# Sheet1.net
KiCad netlist of a schematic drawn in Altium Designer
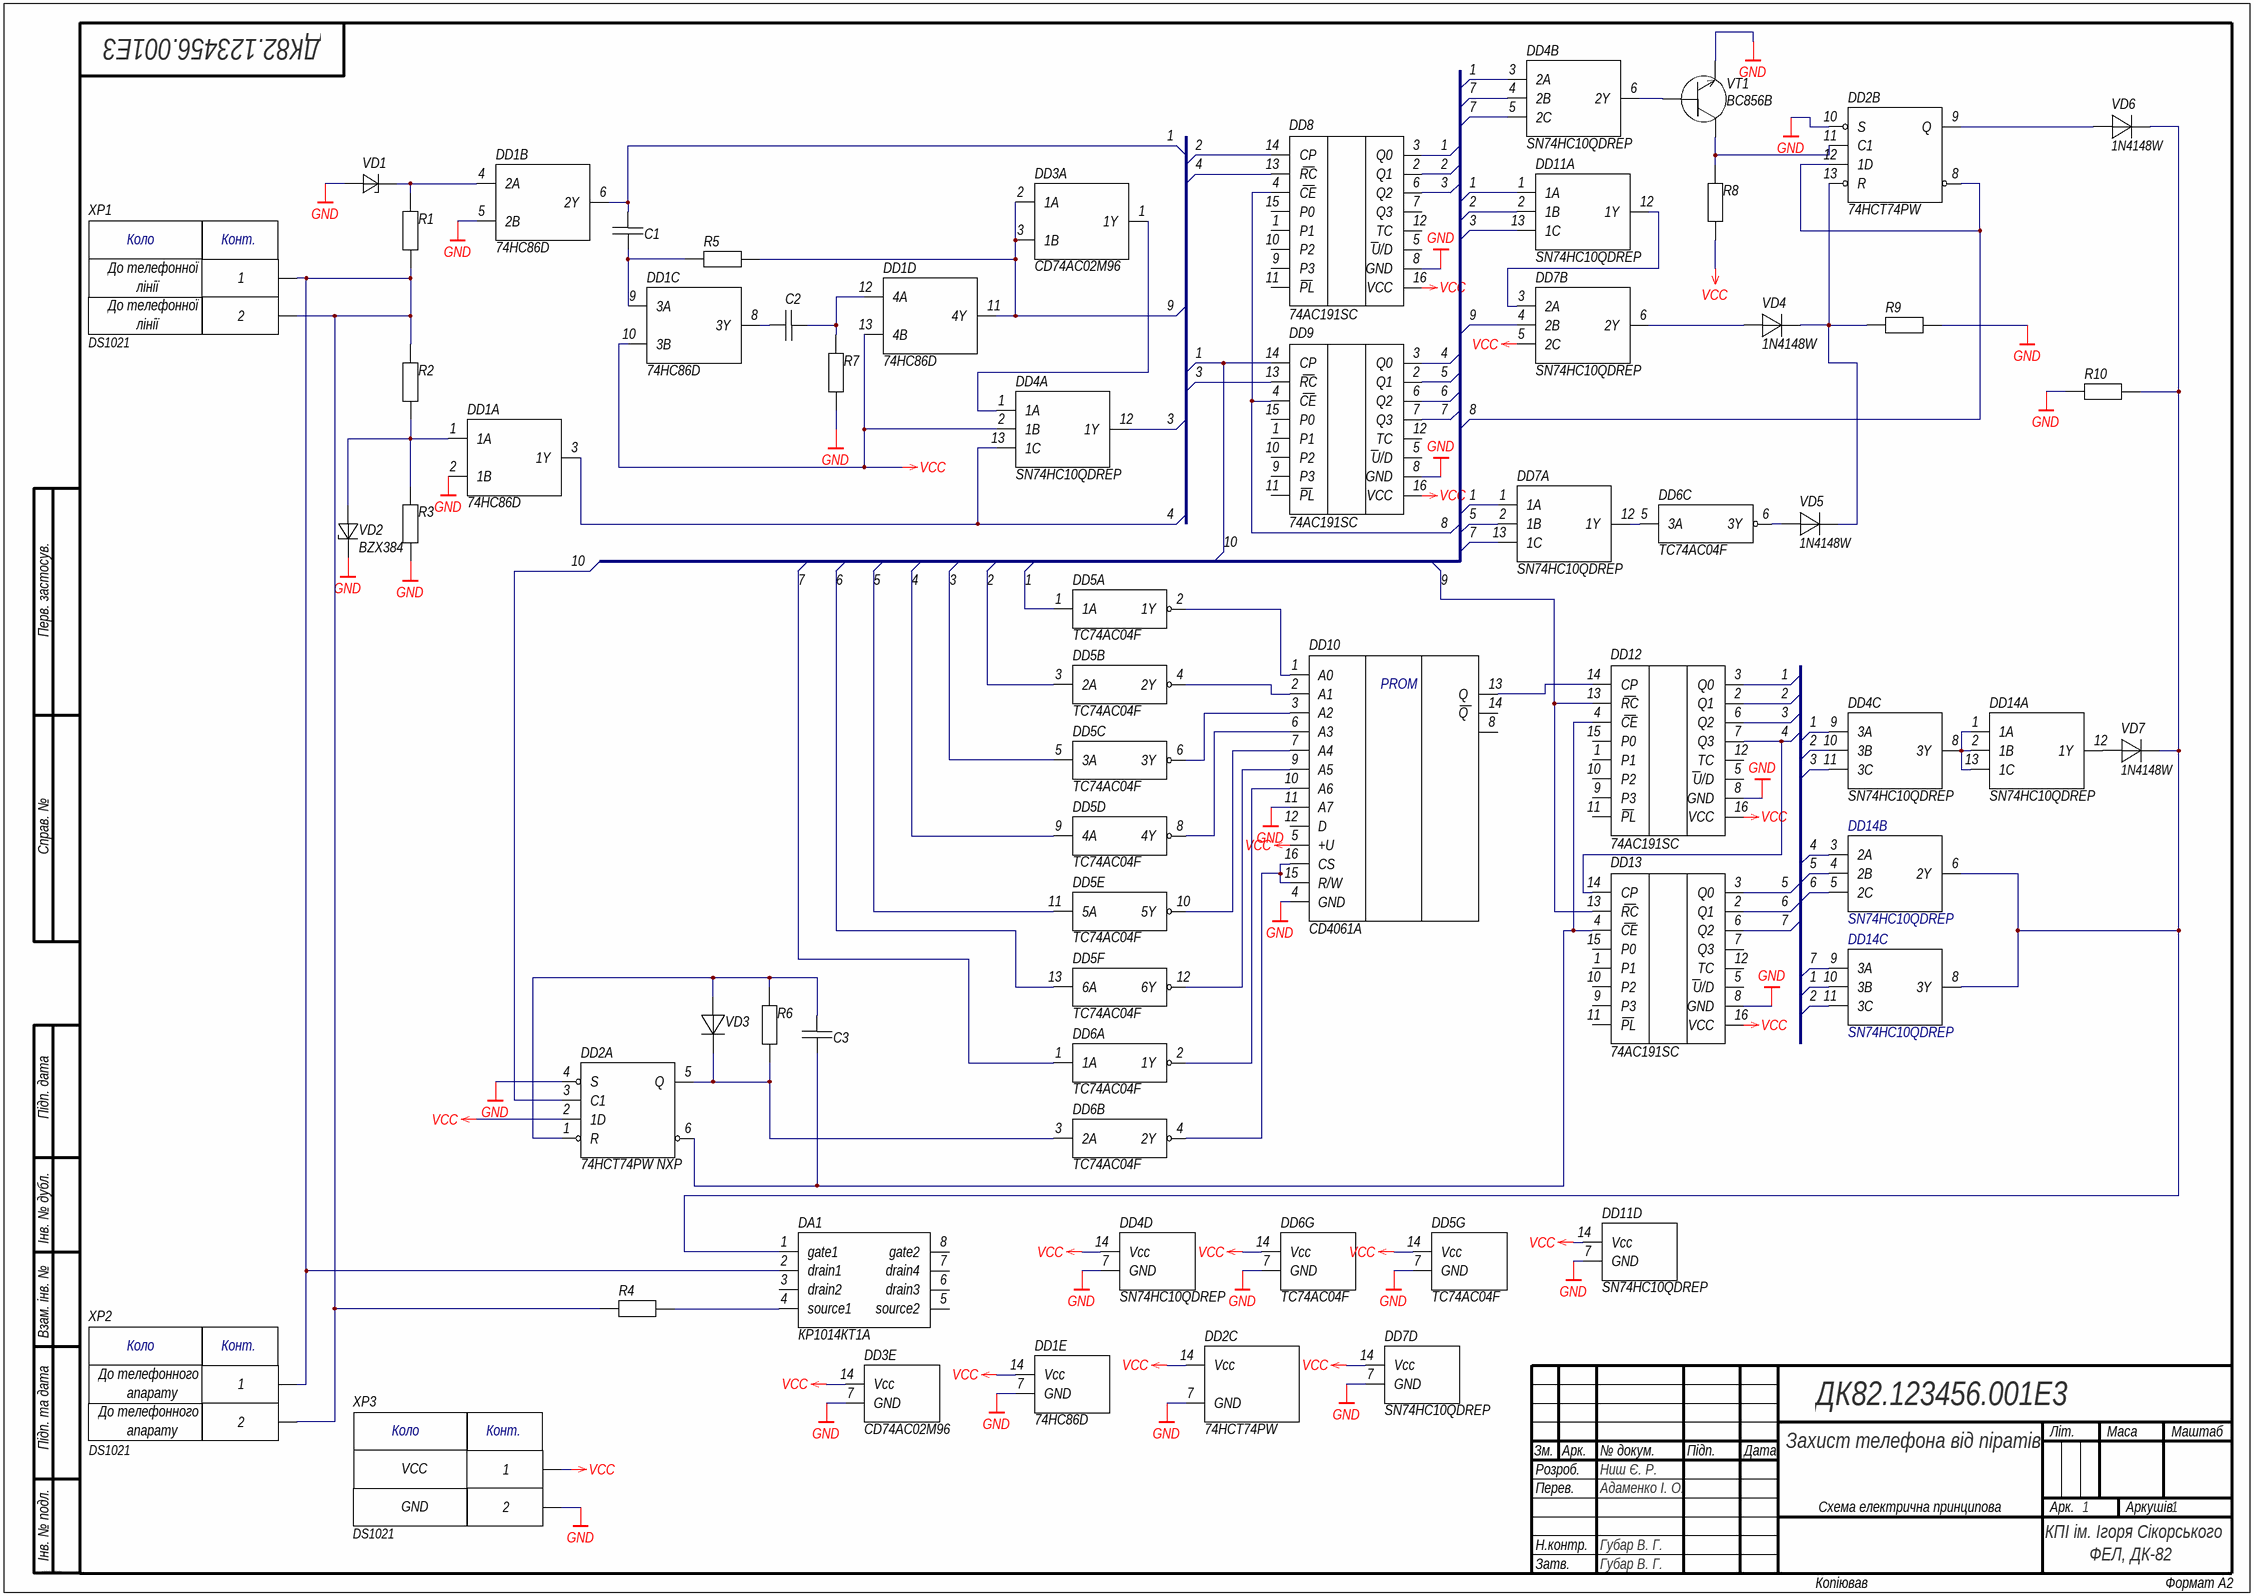
[diagram p0: Sheet1.SchDoc]

(export (version "E")
  (design (tool "Eeschema 10.0.6"))
  (components
    (comp (ref "C1")
      (value "С-0805 50 В 1 мкФ 10% X7R Hitano")
      (footprint "0805")
      (fields
        (field (name "VOLTAGE") "50 В")
        (field (name "TOLERANCE") "10%")
        (field (name "MANUFACTURER") "Hitano")
      )
      (libsource (lib "Schlib1") (part "C-0805 1 мкФ"))
    )
    (comp (ref "C2")
      (value "С-0805 50 В 1 мкФ 10% X7R Hitano")
      (footprint "0805")
      (fields
        (field (name "VOLTAGE") "50 В")
        (field (name "TOLERANCE") "10%")
        (field (name "MANUFACTURER") "Hitano")
      )
      (libsource (lib "Schlib1") (part "C-0805 1 мкФ"))
    )
    (comp (ref "C3")
      (value "С-0805 50 В 1 мкФ 10% X7R Hitano")
      (footprint "0805")
      (fields
        (field (name "VOLTAGE") "50 В")
        (field (name "TOLERANCE") "10%")
        (field (name "MANUFACTURER") "Hitano")
      )
      (libsource (lib "Schlib1") (part "C-0805 1 мкФ"))
    )
    (comp (ref "DA1")
      (value "КР1014КТ1А Электроника и связь")
      (footprint "DIP8")
      (fields (field (name "NAME") "КР1014КТ1А") (field (name "MANUFACTURER") "Электроника и связь"))
      (libsource (lib "Schlib1") (part "КР1014КТ1А"))
    )
    (comp (ref "DD1")
      (value "74HC86D Philips")
      (footprint "SOIC-14")
      (description "OR")
      (fields (field (name "NAME") "74HC86D") (field (name "MANUFACTURER") "Philips"))
      (libsource (lib "Schlib1") (part "74HC86D"))
    )
    (comp (ref "DD2")
      (value "74HCT74PW NXP")
      (footprint "TSSOP-14")
      (description "DUAL D FF POSEDG TRIG")
      (fields (field (name "MANUFACTURER") "NXP") (field (name "NAME") "74HCT74PW"))
      (libsource (lib "Schlib1") (part "74HCT74PW"))
    )
    (comp (ref "DD3")
      (value "CD74AC02M96 TI")
      (footprint "SOIC-14")
      (description "2-INPUT NOR GATE")
      (fields (field (name "NAME") "CD74AC02M96") (field (name "MANUFACTURER") "TI"))
      (libsource (lib "Schlib1") (part "CD74AC02M96"))
    )
    (comp (ref "DD4")
      (value "SN74HC10QDREP Texas Instruments")
      (footprint "SOIC-14")
      (description "3-INPUT NAND GATE")
      (fields (field (name "NAME") "SN74HC10QDREP") (field (name "MANUFACTURER") "Texas Instruments"))
      (libsource (lib "Schlib1") (part "SN74HC10QDREP"))
    )
    (comp (ref "DD5")
      (value "TC74AC04F Toshiba")
      (footprint "SOIC-14")
      (description "NOT")
      (fields (field (name "NAME") "TC74AC04F") (field (name "MANUFACTURER") "Toshiba"))
      (libsource (lib "Schlib1") (part "TC74AC04F"))
    )
    (comp (ref "DD6")
      (value "TC74AC04F Toshiba")
      (footprint "SOIC-14")
      (description "NOT")
      (fields (field (name "NAME") "TC74AC04F") (field (name "MANUFACTURER") "Toshiba"))
      (libsource (lib "Schlib1") (part "TC74AC04F"))
    )
    (comp (ref "DD7")
      (value "SN74HC10QDREP Texas Instruments")
      (footprint "SOIC-14")
      (description "3-INPUT NAND GATE")
      (fields (field (name "NAME") "SN74HC10QDREP") (field (name "MANUFACTURER") "Texas Instruments"))
      (libsource (lib "Schlib1") (part "SN74HC10QDREP"))
    )
    (comp (ref "DD8")
      (value "74AC191SC Fairchild")
      (footprint "SOIC-16")
      (description "Counter")
      (fields (field (name "NAME") "74AC191SC") (field (name "MANUFACTURER") "Fairchild"))
      (libsource (lib "Schlib1") (part "74AC191SC"))
    )
    (comp (ref "DD9")
      (value "74AC191SC Fairchild")
      (footprint "SOIC-16")
      (description "Counter")
      (fields (field (name "NAME") "74AC191SC") (field (name "MANUFACTURER") "Fairchild"))
      (libsource (lib "Schlib1") (part "74AC191SC"))
    )
    (comp (ref "DD10")
      (value "CD4061A NXP")
      (footprint "DIP16")
      (fields (field (name "NAME") "CD4061A") (field (name "MANUFACTURER") "NXP"))
      (libsource (lib "Schlib1") (part "CD4061A"))
    )
    (comp (ref "DD11")
      (value "SN74HC10QDREP Texas Instruments")
      (footprint "SOIC-14")
      (description "3-INPUT NAND GATE")
      (fields (field (name "NAME") "SN74HC10QDREP") (field (name "MANUFACTURER") "Texas Instruments"))
      (libsource (lib "Schlib1") (part "SN74HC10QDREP"))
    )
    (comp (ref "DD12")
      (value "74AC191SC Fairchild")
      (footprint "SOIC-16")
      (description "Counter")
      (fields (field (name "NAME") "74AC191SC") (field (name "MANUFACTURER") "Fairchild"))
      (libsource (lib "Schlib1") (part "74AC191SC"))
    )
    (comp (ref "DD13")
      (value "74AC191SC Fairchild")
      (footprint "SOIC-16")
      (description "Counter")
      (fields (field (name "NAME") "74AC191SC") (field (name "MANUFACTURER") "Fairchild"))
      (libsource (lib "Schlib1") (part "74AC191SC"))
    )
    (comp (ref "DD14")
      (value "SN74HC10QDREP Texas Instruments")
      (footprint "SOIC-14")
      (description "3-INPUT NAND GATE")
      (fields (field (name "NAME") "SN74HC10QDREP") (field (name "MANUFACTURER") "Texas Instruments"))
      (libsource (lib "Schlib1") (part "SN74HC10QDREP"))
    )
    (comp (ref "R1")
      (value "R-0805 0,125 Вт 390 кОм 5 % Hitano")
      (footprint "0805")
      (fields
        (field (name "POWER") "0,125 Вт")
        (field (name "TOLERANCE") "5 %")
        (field (name "MANUFACTURER") "Hitano")
      )
      (libsource (lib "Schlib1") (part "R-0805 390 кОм"))
    )
    (comp (ref "R2")
      (value "R-0805 0,125 Вт 433,5 кОм 5 % Hitano")
      (footprint "0805")
      (fields
        (field (name "POWER") "0,125 Вт")
        (field (name "TOLERANCE") "5 %")
        (field (name "MANUFACTURER") "Hitano")
      )
      (libsource (lib "Schlib1") (part "R-0805 433,5 кОм"))
    )
    (comp (ref "R3")
      (value "R-0805 0,125 Вт 76,5 кОм 5 % Hitano")
      (footprint "0805")
      (fields
        (field (name "POWER") "0,125 Вт")
        (field (name "TOLERANCE") "5 %")
        (field (name "MANUFACTURER") "Hitano")
      )
      (libsource (lib "Schlib1") (part "R-0805 76,5 кОм"))
    )
    (comp (ref "R4")
      (value "R-0805 0,125 Вт 39 кОм 5 % Hitano")
      (footprint "0805")
      (fields
        (field (name "POWER") "0,125 Вт")
        (field (name "TOLERANCE") "5 %")
        (field (name "MANUFACTURER") "Hitano")
      )
      (libsource (lib "Schlib1") (part "R-0805 39 кОм"))
    )
    (comp (ref "R5")
      (value "R-0805 0,125 Вт 100 кОм 5 % Hitano")
      (footprint "0805")
      (fields
        (field (name "POWER") "0,125 Вт")
        (field (name "TOLERANCE") "5 %")
        (field (name "MANUFACTURER") "Hitano")
      )
      (libsource (lib "Schlib1") (part "R-0805 100 кОм"))
    )
    (comp (ref "R6")
      (value "R-0805 0,125 Вт 82 кОм 5 % Hitano")
      (footprint "0805")
      (fields
        (field (name "POWER") "0,125 Вт")
        (field (name "TOLERANCE") "5 %")
        (field (name "MANUFACTURER") "Hitano")
      )
      (libsource (lib "") (part "R-0805 82 кОм_1"))
    )
    (comp (ref "R7")
      (value "R-0805 0,125 Вт 82 кОм 5 % Hitano")
      (footprint "0805")
      (fields
        (field (name "POWER") "0,125 Вт")
        (field (name "TOLERANCE") "5 %")
        (field (name "MANUFACTURER") "Hitano")
      )
      (libsource (lib "Schlib1") (part "R-0805 82 кОм"))
    )
    (comp (ref "R8")
      (value "R-0805 0,125 Вт 100 кОм 5 % Hitano")
      (footprint "0805")
      (fields
        (field (name "POWER") "0,125 Вт")
        (field (name "TOLERANCE") "5 %")
        (field (name "MANUFACTURER") "Hitano")
      )
      (libsource (lib "") (part "R-0805 100 кОм_1"))
    )
    (comp (ref "R9")
      (value "R-0805 0,125 Вт 100 кОм 5 % Hitano")
      (footprint "0805")
      (fields
        (field (name "POWER") "0,125 Вт")
        (field (name "TOLERANCE") "5 %")
        (field (name "MANUFACTURER") "Hitano")
      )
      (libsource (lib "Schlib1") (part "R-0805 100 кОм"))
    )
    (comp (ref "R10")
      (value "R-0805 0,125 Вт 100 кОм 5 % Hitano")
      (footprint "0805")
      (fields
        (field (name "POWER") "0,125 Вт")
        (field (name "TOLERANCE") "5 %")
        (field (name "MANUFACTURER") "Hitano")
      )
      (libsource (lib "Schlib1") (part "R-0805 100 кОм"))
    )
    (comp (ref "VD1")
      (value "BZX384 NXP")
      (footprint "SOD-323")
      (fields (field (name "MANUFACTURER") "NXP"))
      (libsource (lib "Schlib1") (part "BZX384"))
    )
    (comp (ref "VD2")
      (value "BZX384 NXP")
      (footprint "SOD-323")
      (fields (field (name "NAME") "BZX384") (field (name "MANUFACTURER") "NXP"))
      (libsource (lib "Schlib1") (part "BZX384"))
    )
    (comp (ref "VD3")
      (value "1N4148W Yangjie")
      (footprint "SOD-123")
      (description "1N4148W")
      (fields (field (name "MANUFACTURER") "Yangjie"))
      (libsource (lib "Schlib1") (part "1N4148W"))
    )
    (comp (ref "VD4")
      (value "1N4148W Yangjie")
      (footprint "SOD-123")
      (description "1N4148W")
      (fields (field (name "MANUFACTURER") "Yangjie") (field (name "NAME") "1N4148W"))
      (libsource (lib "Schlib1") (part "1N4148W"))
    )
    (comp (ref "VD5")
      (value "1N4148W Yangjie")
      (footprint "SOD-123")
      (description "1N4148W")
      (fields (field (name "MANUFACTURER") "Yangjie") (field (name "NAME") "1N4148W"))
      (libsource (lib "Schlib1") (part "1N4148W"))
    )
    (comp (ref "VD6")
      (value "1N4148W Yangjie")
      (footprint "SOD-123")
      (description "1N4148W")
      (fields (field (name "MANUFACTURER") "Yangjie") (field (name "NAME") "1N4148W"))
      (libsource (lib "Schlib1") (part "1N4148W"))
    )
    (comp (ref "VD7")
      (value "1N4148W Yangjie")
      (footprint "SOD-123")
      (description "1N4148W")
      (fields (field (name "MANUFACTURER") "Yangjie") (field (name "NAME") "1N4148W"))
      (libsource (lib "Schlib1") (part "1N4148W"))
    )
    (comp (ref "VT1")
      (value "BC856B Infineon")
      (footprint "SOT-23")
      (fields (field (name "NAME") "BC856B") (field (name "MANUFACTURER") "Infineon"))
      (libsource (lib "Schlib1") (part "BC856B"))
    )
    (comp (ref "XP1")
      (value "DS1021 Ningbo Zhenqin Electronic")
      (footprint "PLS-2")
      (description "PLS-2_1x2")
      (fields (field (name "MANUFACTURER") "Ningbo Zhenqin Electronic") (field (name "NAME") "DS1021"))
      (libsource (lib "Schlib1") (part "DS1021"))
    )
    (comp (ref "XP2")
      (value "DS1021 Ningbo Zhenqin Electronic")
      (footprint "PLS-2")
      (description "PLS-2_1x2")
      (fields (field (name "MANUFACTURER") "Ningbo Zhenqin Electronic") (field (name "NAME") "DS1021"))
      (libsource (lib "Schlib1") (part "DS1021"))
    )
    (comp (ref "XP3")
      (value "DS1021 Ningbo Zhenqin Electronic")
      (footprint "PLS-2")
      (description "PLS-2_1x2")
      (fields (field (name "MANUFACTURER") "Ningbo Zhenqin Electronic") (field (name "NAME") "DS1021"))
      (libsource (lib "Schlib1") (part "DS1021"))
    )
  )
  (nets
    (net (code "1") (name "/1") (class "Default")
      (node (ref "C1") (pin "2") (pintype "passive"))
      (node (ref "DD1") (pin "6") (pinfunction "2Y_6") (pintype "passive"))
      (node (ref "DD11") (pin "1") (pinfunction "1A_1") (pintype "passive"))
      (node (ref "DD12") (pin "3") (pinfunction "Q0_3") (pintype "passive"))
      (node (ref "DD14") (pin "10") (pinfunction "3B_10") (pintype "passive"))
      (node (ref "DD2") (pin "3") (pinfunction "C1_3") (pintype "passive"))
      (node (ref "DD4") (pin "3") (pinfunction "2A_3") (pintype "passive"))
      (node (ref "DD4") (pin "9") (pinfunction "3A_9") (pintype "passive"))
      (node (ref "DD5") (pin "1") (pinfunction "1A_1") (pintype "passive"))
      (node (ref "DD7") (pin "1") (pinfunction "1A_1") (pintype "passive"))
      (node (ref "DD8") (pin "3") (pinfunction "Q0_3") (pintype "passive"))
      (node (ref "DD9") (pin "14") (pinfunction "CP_14") (pintype "passive"))
    )
    (net (code "2") (name "/2") (class "Default")
      (node (ref "DD11") (pin "2") (pinfunction "1B_2") (pintype "passive"))
      (node (ref "DD12") (pin "2") (pinfunction "Q1_2") (pintype "passive"))
      (node (ref "DD14") (pin "11") (pinfunction "3C_11") (pintype "passive"))
      (node (ref "DD4") (pin "10") (pinfunction "3B_10") (pintype "passive"))
      (node (ref "DD5") (pin "3") (pinfunction "2A_3") (pintype "passive"))
      (node (ref "DD8") (pin "14") (pinfunction "CP_14") (pintype "passive"))
      (node (ref "DD8") (pin "2") (pinfunction "Q1_2") (pintype "passive"))
    )
    (net (code "3") (name "/3") (class "Default")
      (node (ref "DD11") (pin "13") (pinfunction "1C_13") (pintype "passive"))
      (node (ref "DD12") (pin "6") (pinfunction "Q2_6") (pintype "passive"))
      (node (ref "DD4") (pin "11") (pinfunction "3C_11") (pintype "passive"))
      (node (ref "DD4") (pin "12") (pinfunction "1Y_12") (pintype "passive"))
      (node (ref "DD5") (pin "5") (pinfunction "3A_5") (pintype "passive"))
      (node (ref "DD8") (pin "6") (pinfunction "Q2_6") (pintype "passive"))
      (node (ref "DD9") (pin "13") (pinfunction "RC_13") (pintype "passive"))
    )
    (net (code "4") (name "/4") (class "Default")
      (node (ref "DD1") (pin "3") (pinfunction "1Y_3") (pintype "passive"))
      (node (ref "DD12") (pin "7") (pinfunction "Q3_7") (pintype "passive"))
      (node (ref "DD13") (pin "14") (pinfunction "CP_14") (pintype "passive"))
      (node (ref "DD14") (pin "3") (pinfunction "2A_3") (pintype "passive"))
      (node (ref "DD4") (pin "13") (pinfunction "1C_13") (pintype "passive"))
      (node (ref "DD5") (pin "9") (pinfunction "4A_9") (pintype "passive"))
      (node (ref "DD8") (pin "13") (pinfunction "RC_13") (pintype "passive"))
      (node (ref "DD9") (pin "3") (pinfunction "Q0_3") (pintype "passive"))
    )
    (net (code "5") (name "/5") (class "Default")
      (node (ref "DD13") (pin "3") (pinfunction "Q0_3") (pintype "passive"))
      (node (ref "DD14") (pin "4") (pinfunction "2B_4") (pintype "passive"))
      (node (ref "DD5") (pin "11") (pinfunction "5A_11") (pintype "passive"))
      (node (ref "DD7") (pin "2") (pinfunction "1B_2") (pintype "passive"))
      (node (ref "DD9") (pin "2") (pinfunction "Q1_2") (pintype "passive"))
    )
    (net (code "6") (name "/6") (class "Default")
      (node (ref "DD13") (pin "2") (pinfunction "Q1_2") (pintype "passive"))
      (node (ref "DD14") (pin "5") (pinfunction "2C_5") (pintype "passive"))
      (node (ref "DD5") (pin "13") (pinfunction "6A_13") (pintype "passive"))
      (node (ref "DD9") (pin "6") (pinfunction "Q2_6") (pintype "passive"))
    )
    (net (code "7") (name "/7") (class "Default")
      (node (ref "DD13") (pin "6") (pinfunction "Q2_6") (pintype "passive"))
      (node (ref "DD14") (pin "9") (pinfunction "3A_9") (pintype "passive"))
      (node (ref "DD4") (pin "4") (pinfunction "2B_4") (pintype "passive"))
      (node (ref "DD4") (pin "5") (pinfunction "2C_5") (pintype "passive"))
      (node (ref "DD6") (pin "1") (pinfunction "1A_1") (pintype "passive"))
      (node (ref "DD7") (pin "13") (pinfunction "1C_13") (pintype "passive"))
      (node (ref "DD9") (pin "7") (pinfunction "Q3_7") (pintype "passive"))
    )
    (net (code "8") (name "/8") (class "Default")
      (node (ref "DD2") (pin "12") (pinfunction "1D_12") (pintype "passive"))
      (node (ref "DD2") (pin "8") (pinfunction "Q_8") (pintype "passive"))
      (node (ref "DD8") (pin "4") (pinfunction "CE_4") (pintype "passive"))
      (node (ref "DD9") (pin "4") (pinfunction "CE_4") (pintype "passive"))
    )
    (net (code "9") (name "/9") (class "Default")
      (node (ref "DD1") (pin "11") (pinfunction "4Y_11") (pintype "passive"))
      (node (ref "DD12") (pin "13") (pinfunction "RC_13") (pintype "passive"))
      (node (ref "DD13") (pin "13") (pinfunction "RC_13") (pintype "passive"))
      (node (ref "DD3") (pin "2") (pinfunction "1A_2") (pintype "passive"))
      (node (ref "DD3") (pin "3") (pinfunction "1B_3") (pintype "passive"))
      (node (ref "DD7") (pin "4") (pinfunction "2B_4") (pintype "passive"))
      (node (ref "R5") (pin "2") (pinfunction "2_2") (pintype "passive"))
    )
    (net (code "10") (name "GND") (class "Default")
      (node (ref "DD1") (pin "2") (pinfunction "1B_2") (pintype "passive"))
      (node (ref "DD1") (pin "5") (pinfunction "2B_5") (pintype "passive"))
      (node (ref "DD1") (pin "7") (pinfunction "GND_7") (pintype "passive"))
      (node (ref "DD10") (pin "11") (pinfunction "A7_11") (pintype "passive"))
      (node (ref "DD10") (pin "4") (pinfunction "GND_4") (pintype "passive"))
      (node (ref "DD11") (pin "7") (pinfunction "GND_7") (pintype "passive"))
      (node (ref "DD12") (pin "8") (pinfunction "GND_8") (pintype "passive"))
      (node (ref "DD13") (pin "8") (pinfunction "GND_8") (pintype "passive"))
      (node (ref "DD2") (pin "10") (pinfunction "S_10") (pintype "passive"))
      (node (ref "DD2") (pin "4") (pinfunction "S_4") (pintype "passive"))
      (node (ref "DD2") (pin "7") (pinfunction "GND_7") (pintype "passive"))
      (node (ref "DD3") (pin "7") (pinfunction "GND_7") (pintype "passive"))
      (node (ref "DD4") (pin "7") (pinfunction "GND_7") (pintype "passive"))
      (node (ref "DD5") (pin "7") (pinfunction "GND_7") (pintype "passive"))
      (node (ref "DD6") (pin "7") (pinfunction "GND_7") (pintype "passive"))
      (node (ref "DD7") (pin "7") (pinfunction "GND_7") (pintype "passive"))
      (node (ref "DD8") (pin "8") (pinfunction "GND_8") (pintype "passive"))
      (node (ref "DD9") (pin "8") (pinfunction "GND_8") (pintype "passive"))
      (node (ref "R10") (pin "1") (pinfunction "1_1") (pintype "passive"))
      (node (ref "R3") (pin "1") (pinfunction "1_1") (pintype "passive"))
      (node (ref "R7") (pin "2") (pinfunction "2_2") (pintype "passive"))
      (node (ref "R9") (pin "2") (pinfunction "2_2") (pintype "passive"))
      (node (ref "VD1") (pin "1") (pinfunction "1_1") (pintype "passive"))
      (node (ref "VD2") (pin "2") (pinfunction "2_2") (pintype "passive"))
      (node (ref "VT1") (pin "2") (pinfunction "2_2") (pintype "passive"))
      (node (ref "XP3") (pin "2") (pinfunction "2_2") (pintype "passive"))
    )
    (net (code "11") (name "Net-(DA1-drain1)") (class "Default")
      (node (ref "DA1") (pin "2") (pinfunction "drain1_2") (pintype "passive"))
      (node (ref "R1") (pin "1") (pinfunction "1_1") (pintype "passive"))
      (node (ref "R2") (pin "2") (pinfunction "2_2") (pintype "passive"))
      (node (ref "R4") (pin "1") (pinfunction "1_1") (pintype "passive"))
      (node (ref "XP1") (pin "1") (pinfunction "1_1") (pintype "passive"))
      (node (ref "XP1") (pin "2") (pinfunction "2_2") (pintype "passive"))
      (node (ref "XP2") (pin "1") (pinfunction "1_1") (pintype "passive"))
      (node (ref "XP2") (pin "2") (pinfunction "2_2") (pintype "passive"))
    )
    (net (code "12") (name "Net-(DA1-gate1)") (class "Default")
      (node (ref "DA1") (pin "1") (pinfunction "gate1_1") (pintype "passive"))
      (node (ref "DD14") (pin "6") (pinfunction "2Y_6") (pintype "passive"))
      (node (ref "DD14") (pin "8") (pinfunction "3Y_8") (pintype "passive"))
      (node (ref "R10") (pin "2") (pinfunction "2_2") (pintype "passive"))
      (node (ref "VD6") (pin "2") (pinfunction "2_2") (pintype "passive"))
      (node (ref "VD7") (pin "2") (pinfunction "2_2") (pintype "passive"))
    )
    (net (code "13") (name "Net-(DA1-source1)") (class "Default")
      (node (ref "DA1") (pin "4") (pinfunction "source1_4") (pintype "passive"))
      (node (ref "R4") (pin "2") (pinfunction "2_2") (pintype "passive"))
    )
    (net (code "14") (name "Net-(DD1A-1A)") (class "Default")
      (node (ref "DD1") (pin "1") (pinfunction "1A_1") (pintype "passive"))
      (node (ref "R2") (pin "1") (pinfunction "1_1") (pintype "passive"))
      (node (ref "R3") (pin "2") (pinfunction "2_2") (pintype "passive"))
      (node (ref "VD2") (pin "1") (pinfunction "1_1") (pintype "passive"))
    )
    (net (code "15") (name "Net-(DD1B-2A)") (class "Default")
      (node (ref "DD1") (pin "4") (pinfunction "2A_4") (pintype "passive"))
      (node (ref "R1") (pin "2") (pinfunction "2_2") (pintype "passive"))
      (node (ref "VD1") (pin "2") (pinfunction "2_2") (pintype "passive"))
    )
    (net (code "16") (name "Net-(DD1C-3A)") (class "Default")
      (node (ref "C1") (pin "1") (pintype "passive"))
      (node (ref "DD1") (pin "9") (pinfunction "3A_9") (pintype "passive"))
      (node (ref "R5") (pin "1") (pinfunction "1_1") (pintype "passive"))
    )
    (net (code "17") (name "Net-(DD1C-3Y)") (class "Default")
      (node (ref "C2") (pin "1") (pintype "passive"))
      (node (ref "DD1") (pin "8") (pinfunction "3Y_8") (pintype "passive"))
    )
    (net (code "18") (name "Net-(DD1D-4A)") (class "Default")
      (node (ref "C2") (pin "2") (pintype "passive"))
      (node (ref "DD1") (pin "12") (pinfunction "4A_12") (pintype "passive"))
      (node (ref "R7") (pin "1") (pinfunction "1_1") (pintype "passive"))
    )
    (net (code "19") (name "Net-(DD2A-R)") (class "Default")
      (node (ref "C3") (pin "2") (pintype "passive"))
      (node (ref "DD2") (pin "1") (pinfunction "R_1") (pintype "passive"))
      (node (ref "R6") (pin "2") (pinfunction "2_2") (pintype "passive"))
      (node (ref "VD3") (pin "1") (pinfunction "1_1") (pintype "passive"))
    )
    (net (code "20") (name "Net-(DD2B-C1)") (class "Default")
      (node (ref "DD2") (pin "11") (pinfunction "C1_11") (pintype "passive"))
      (node (ref "R8") (pin "1") (pinfunction "1_1") (pintype "passive"))
      (node (ref "VT1") (pin "3") (pinfunction "3_3") (pintype "passive"))
    )
    (net (code "21") (name "Net-(DD2B-Q-Pad9)") (class "Default")
      (node (ref "DD2") (pin "9") (pinfunction "Q_9") (pintype "passive"))
      (node (ref "VD6") (pin "1") (pinfunction "1_1") (pintype "passive"))
    )
    (net (code "22") (name "Net-(DD2B-R)") (class "Default")
      (node (ref "DD2") (pin "13") (pinfunction "R_13") (pintype "passive"))
      (node (ref "R9") (pin "1") (pinfunction "1_1") (pintype "passive"))
      (node (ref "VD4") (pin "2") (pinfunction "2_2") (pintype "passive"))
      (node (ref "VD5") (pin "2") (pinfunction "2_2") (pintype "passive"))
    )
    (net (code "23") (name "Net-(DD3A-1Y)") (class "Default")
      (node (ref "DD3") (pin "1") (pinfunction "1Y_1") (pintype "passive"))
      (node (ref "DD4") (pin "1") (pinfunction "1A_1") (pintype "passive"))
    )
    (net (code "24") (name "Net-(DD4B-2Y)") (class "Default")
      (node (ref "DD4") (pin "6") (pinfunction "2Y_6") (pintype "passive"))
      (node (ref "VT1") (pin "1") (pinfunction "1_1") (pintype "passive"))
    )
    (net (code "25") (name "Net-(DD6B-2A)") (class "Default")
      (node (ref "DD2") (pin "5") (pinfunction "Q_5") (pintype "passive"))
      (node (ref "DD6") (pin "3") (pinfunction "2A_3") (pintype "passive"))
      (node (ref "R6") (pin "1") (pinfunction "1_1") (pintype "passive"))
      (node (ref "VD3") (pin "2") (pinfunction "2_2") (pintype "passive"))
    )
    (net (code "26") (name "Net-(DD6C-3A)") (class "Default")
      (node (ref "DD6") (pin "5") (pinfunction "3A_5") (pintype "passive"))
      (node (ref "DD7") (pin "12") (pinfunction "1Y_12") (pintype "passive"))
    )
    (net (code "27") (name "Net-(DD6C-3Y)") (class "Default")
      (node (ref "DD6") (pin "6") (pinfunction "3Y_6") (pintype "passive"))
      (node (ref "VD5") (pin "1") (pinfunction "1_1") (pintype "passive"))
    )
    (net (code "28") (name "Net-(DD7B-2Y)") (class "Default")
      (node (ref "DD7") (pin "6") (pinfunction "2Y_6") (pintype "passive"))
      (node (ref "VD4") (pin "1") (pinfunction "1_1") (pintype "passive"))
    )
    (net (code "29") (name "Net-(DD10-A0)") (class "Default")
      (node (ref "DD10") (pin "1") (pinfunction "A0_1") (pintype "passive"))
      (node (ref "DD5") (pin "2") (pinfunction "1Y_2") (pintype "passive"))
    )
    (net (code "30") (name "Net-(DD10-A1)") (class "Default")
      (node (ref "DD10") (pin "2") (pinfunction "A1_2") (pintype "passive"))
      (node (ref "DD5") (pin "4") (pinfunction "2Y_4") (pintype "passive"))
    )
    (net (code "31") (name "Net-(DD10-A2)") (class "Default")
      (node (ref "DD10") (pin "3") (pinfunction "A2_3") (pintype "passive"))
      (node (ref "DD5") (pin "6") (pinfunction "3Y_6") (pintype "passive"))
    )
    (net (code "32") (name "Net-(DD10-A3)") (class "Default")
      (node (ref "DD10") (pin "6") (pinfunction "A3_6") (pintype "passive"))
      (node (ref "DD5") (pin "8") (pinfunction "4Y_8") (pintype "passive"))
    )
    (net (code "33") (name "Net-(DD10-A4)") (class "Default")
      (node (ref "DD10") (pin "7") (pinfunction "A4_7") (pintype "passive"))
      (node (ref "DD5") (pin "10") (pinfunction "5Y_10") (pintype "passive"))
    )
    (net (code "34") (name "Net-(DD10-A5)") (class "Default")
      (node (ref "DD10") (pin "9") (pinfunction "A5_9") (pintype "passive"))
      (node (ref "DD5") (pin "12") (pinfunction "6Y_12") (pintype "passive"))
    )
    (net (code "35") (name "Net-(DD10-A6)") (class "Default")
      (node (ref "DD10") (pin "10") (pinfunction "A6_10") (pintype "passive"))
      (node (ref "DD6") (pin "2") (pinfunction "1Y_2") (pintype "passive"))
    )
    (net (code "36") (name "Net-(DD10-CS)") (class "Default")
      (node (ref "DD10") (pin "15") (pinfunction "R/W_15") (pintype "passive"))
      (node (ref "DD10") (pin "16") (pinfunction "CS_16") (pintype "passive"))
      (node (ref "DD6") (pin "4") (pinfunction "2Y_4") (pintype "passive"))
    )
    (net (code "37") (name "Net-(DD11A-1Y)") (class "Default")
      (node (ref "DD11") (pin "12") (pinfunction "1Y_12") (pintype "passive"))
      (node (ref "DD7") (pin "3") (pinfunction "2A_3") (pintype "passive"))
    )
    (net (code "38") (name "Net-(DD12-CE)") (class "Default")
      (node (ref "C3") (pin "1") (pintype "passive"))
      (node (ref "DD12") (pin "4") (pinfunction "CE_4") (pintype "passive"))
      (node (ref "DD13") (pin "4") (pinfunction "CE_4") (pintype "passive"))
      (node (ref "DD2") (pin "6") (pinfunction "Q_6") (pintype "passive"))
    )
    (net (code "39") (name "Net-(DD12-CP)") (class "Default")
      (node (ref "DD10") (pin "13") (pinfunction "Q_13") (pintype "passive"))
      (node (ref "DD12") (pin "14") (pinfunction "CP_14") (pintype "passive"))
    )
    (net (code "40") (name "Net-(DD14A-1A)") (class "Default")
      (node (ref "DD14") (pin "1") (pinfunction "1A_1") (pintype "passive"))
      (node (ref "DD14") (pin "13") (pinfunction "1C_13") (pintype "passive"))
      (node (ref "DD14") (pin "2") (pinfunction "1B_2") (pintype "passive"))
      (node (ref "DD4") (pin "8") (pinfunction "3Y_8") (pintype "passive"))
    )
    (net (code "41") (name "Net-(DD14A-1Y)") (class "Default")
      (node (ref "DD14") (pin "12") (pinfunction "1Y_12") (pintype "passive"))
      (node (ref "VD7") (pin "1") (pinfunction "1_1") (pintype "passive"))
    )
    (net (code "42") (name "VCC") (class "Default")
      (node (ref "DD1") (pin "10") (pinfunction "3B_10") (pintype "passive"))
      (node (ref "DD1") (pin "13") (pinfunction "4B_13") (pintype "passive"))
      (node (ref "DD1") (pin "14") (pinfunction "Vcc_14") (pintype "passive"))
      (node (ref "DD10") (pin "5") (pinfunction "+U_5") (pintype "passive"))
      (node (ref "DD11") (pin "14") (pinfunction "Vcc_14") (pintype "passive"))
      (node (ref "DD12") (pin "16") (pinfunction "VCC_16") (pintype "passive"))
      (node (ref "DD13") (pin "16") (pinfunction "VCC_16") (pintype "passive"))
      (node (ref "DD2") (pin "14") (pinfunction "Vcc_14") (pintype "passive"))
      (node (ref "DD2") (pin "2") (pinfunction "1D_2") (pintype "passive"))
      (node (ref "DD3") (pin "14") (pinfunction "Vcc_14") (pintype "passive"))
      (node (ref "DD4") (pin "14") (pinfunction "Vcc_14") (pintype "passive"))
      (node (ref "DD4") (pin "2") (pinfunction "1B_2") (pintype "passive"))
      (node (ref "DD5") (pin "14") (pinfunction "Vcc_14") (pintype "passive"))
      (node (ref "DD6") (pin "14") (pinfunction "Vcc_14") (pintype "passive"))
      (node (ref "DD7") (pin "14") (pinfunction "Vcc_14") (pintype "passive"))
      (node (ref "DD7") (pin "5") (pinfunction "2C_5") (pintype "passive"))
      (node (ref "DD8") (pin "16") (pinfunction "VCC_16") (pintype "passive"))
      (node (ref "DD9") (pin "16") (pinfunction "VCC_16") (pintype "passive"))
      (node (ref "R8") (pin "2") (pinfunction "2_2") (pintype "passive"))
      (node (ref "XP3") (pin "1") (pinfunction "1_1") (pintype "passive"))
    )
    (net (code "43") (name "unconnected-(DA1-drain2-Pad3)") (class "Default")
      (node (ref "DA1") (pin "3") (pinfunction "drain2_3") (pintype "passive"))
    )
    (net (code "44") (name "unconnected-(DA1-drain3-Pad6)") (class "Default")
      (node (ref "DA1") (pin "6") (pinfunction "drain3_6") (pintype "passive"))
    )
    (net (code "45") (name "unconnected-(DA1-drain4-Pad7)") (class "Default")
      (node (ref "DA1") (pin "7") (pinfunction "drain4_7") (pintype "passive"))
    )
    (net (code "46") (name "unconnected-(DA1-gate2-Pad8)") (class "Default")
      (node (ref "DA1") (pin "8") (pinfunction "gate2_8") (pintype "passive"))
    )
    (net (code "47") (name "unconnected-(DA1-source2-Pad5)") (class "Default")
      (node (ref "DA1") (pin "5") (pinfunction "source2_5") (pintype "passive"))
    )
    (net (code "48") (name "unconnected-(DD8-P0-Pad15)") (class "Default")
      (node (ref "DD8") (pin "15") (pinfunction "P0_15") (pintype "passive"))
    )
    (net (code "49") (name "unconnected-(DD8-P1-Pad1)") (class "Default")
      (node (ref "DD8") (pin "1") (pinfunction "P1_1") (pintype "passive"))
    )
    (net (code "50") (name "unconnected-(DD8-P2-Pad10)") (class "Default")
      (node (ref "DD8") (pin "10") (pinfunction "P2_10") (pintype "passive"))
    )
    (net (code "51") (name "unconnected-(DD8-P3-Pad9)") (class "Default")
      (node (ref "DD8") (pin "9") (pinfunction "P3_9") (pintype "passive"))
    )
    (net (code "52") (name "unconnected-(DD8-PL-Pad11)") (class "Default")
      (node (ref "DD8") (pin "11") (pinfunction "PL_11") (pintype "passive"))
    )
    (net (code "53") (name "unconnected-(DD8-Q3-Pad7)") (class "Default")
      (node (ref "DD8") (pin "7") (pinfunction "Q3_7") (pintype "passive"))
    )
    (net (code "54") (name "unconnected-(DD8-TC-Pad12)") (class "Default")
      (node (ref "DD8") (pin "12") (pinfunction "TC_12") (pintype "passive"))
    )
    (net (code "55") (name "unconnected-(DD8-U{slash}D-Pad5)") (class "Default")
      (node (ref "DD8") (pin "5") (pinfunction "U/D_5") (pintype "passive"))
    )
    (net (code "56") (name "unconnected-(DD9-P0-Pad15)") (class "Default")
      (node (ref "DD9") (pin "15") (pinfunction "P0_15") (pintype "passive"))
    )
    (net (code "57") (name "unconnected-(DD9-P1-Pad1)") (class "Default")
      (node (ref "DD9") (pin "1") (pinfunction "P1_1") (pintype "passive"))
    )
    (net (code "58") (name "unconnected-(DD9-P2-Pad10)") (class "Default")
      (node (ref "DD9") (pin "10") (pinfunction "P2_10") (pintype "passive"))
    )
    (net (code "59") (name "unconnected-(DD9-P3-Pad9)") (class "Default")
      (node (ref "DD9") (pin "9") (pinfunction "P3_9") (pintype "passive"))
    )
    (net (code "60") (name "unconnected-(DD9-PL-Pad11)") (class "Default")
      (node (ref "DD9") (pin "11") (pinfunction "PL_11") (pintype "passive"))
    )
    (net (code "61") (name "unconnected-(DD9-TC-Pad12)") (class "Default")
      (node (ref "DD9") (pin "12") (pinfunction "TC_12") (pintype "passive"))
    )
    (net (code "62") (name "unconnected-(DD9-U{slash}D-Pad5)") (class "Default")
      (node (ref "DD9") (pin "5") (pinfunction "U/D_5") (pintype "passive"))
    )
    (net (code "63") (name "unconnected-(DD10-D-Pad12)") (class "Default")
      (node (ref "DD10") (pin "12") (pinfunction "D_12") (pintype "passive"))
    )
    (net (code "64") (name "unconnected-(DD10-Pad8)") (class "Default")
      (node (ref "DD10") (pin "8") (pintype "passive"))
    )
    (net (code "65") (name "unconnected-(DD10-Q-Pad14)") (class "Default")
      (node (ref "DD10") (pin "14") (pinfunction "Q_14") (pintype "passive"))
    )
    (net (code "66") (name "unconnected-(DD12-P0-Pad15)") (class "Default")
      (node (ref "DD12") (pin "15") (pinfunction "P0_15") (pintype "passive"))
    )
    (net (code "67") (name "unconnected-(DD12-P1-Pad1)") (class "Default")
      (node (ref "DD12") (pin "1") (pinfunction "P1_1") (pintype "passive"))
    )
    (net (code "68") (name "unconnected-(DD12-P2-Pad10)") (class "Default")
      (node (ref "DD12") (pin "10") (pinfunction "P2_10") (pintype "passive"))
    )
    (net (code "69") (name "unconnected-(DD12-P3-Pad9)") (class "Default")
      (node (ref "DD12") (pin "9") (pinfunction "P3_9") (pintype "passive"))
    )
    (net (code "70") (name "unconnected-(DD12-PL-Pad11)") (class "Default")
      (node (ref "DD12") (pin "11") (pinfunction "PL_11") (pintype "passive"))
    )
    (net (code "71") (name "unconnected-(DD12-TC-Pad12)") (class "Default")
      (node (ref "DD12") (pin "12") (pinfunction "TC_12") (pintype "passive"))
    )
    (net (code "72") (name "unconnected-(DD12-U{slash}D-Pad5)") (class "Default")
      (node (ref "DD12") (pin "5") (pinfunction "U/D_5") (pintype "passive"))
    )
    (net (code "73") (name "unconnected-(DD13-P0-Pad15)") (class "Default")
      (node (ref "DD13") (pin "15") (pinfunction "P0_15") (pintype "passive"))
    )
    (net (code "74") (name "unconnected-(DD13-P1-Pad1)") (class "Default")
      (node (ref "DD13") (pin "1") (pinfunction "P1_1") (pintype "passive"))
    )
    (net (code "75") (name "unconnected-(DD13-P2-Pad10)") (class "Default")
      (node (ref "DD13") (pin "10") (pinfunction "P2_10") (pintype "passive"))
    )
    (net (code "76") (name "unconnected-(DD13-P3-Pad9)") (class "Default")
      (node (ref "DD13") (pin "9") (pinfunction "P3_9") (pintype "passive"))
    )
    (net (code "77") (name "unconnected-(DD13-PL-Pad11)") (class "Default")
      (node (ref "DD13") (pin "11") (pinfunction "PL_11") (pintype "passive"))
    )
    (net (code "78") (name "unconnected-(DD13-Q3-Pad7)") (class "Default")
      (node (ref "DD13") (pin "7") (pinfunction "Q3_7") (pintype "passive"))
    )
    (net (code "79") (name "unconnected-(DD13-TC-Pad12)") (class "Default")
      (node (ref "DD13") (pin "12") (pinfunction "TC_12") (pintype "passive"))
    )
    (net (code "80") (name "unconnected-(DD13-U{slash}D-Pad5)") (class "Default")
      (node (ref "DD13") (pin "5") (pinfunction "U/D_5") (pintype "passive"))
    )
  )
)
